# MCU_IO.net
KiCad netlist of a schematic drawn in Altium Designer
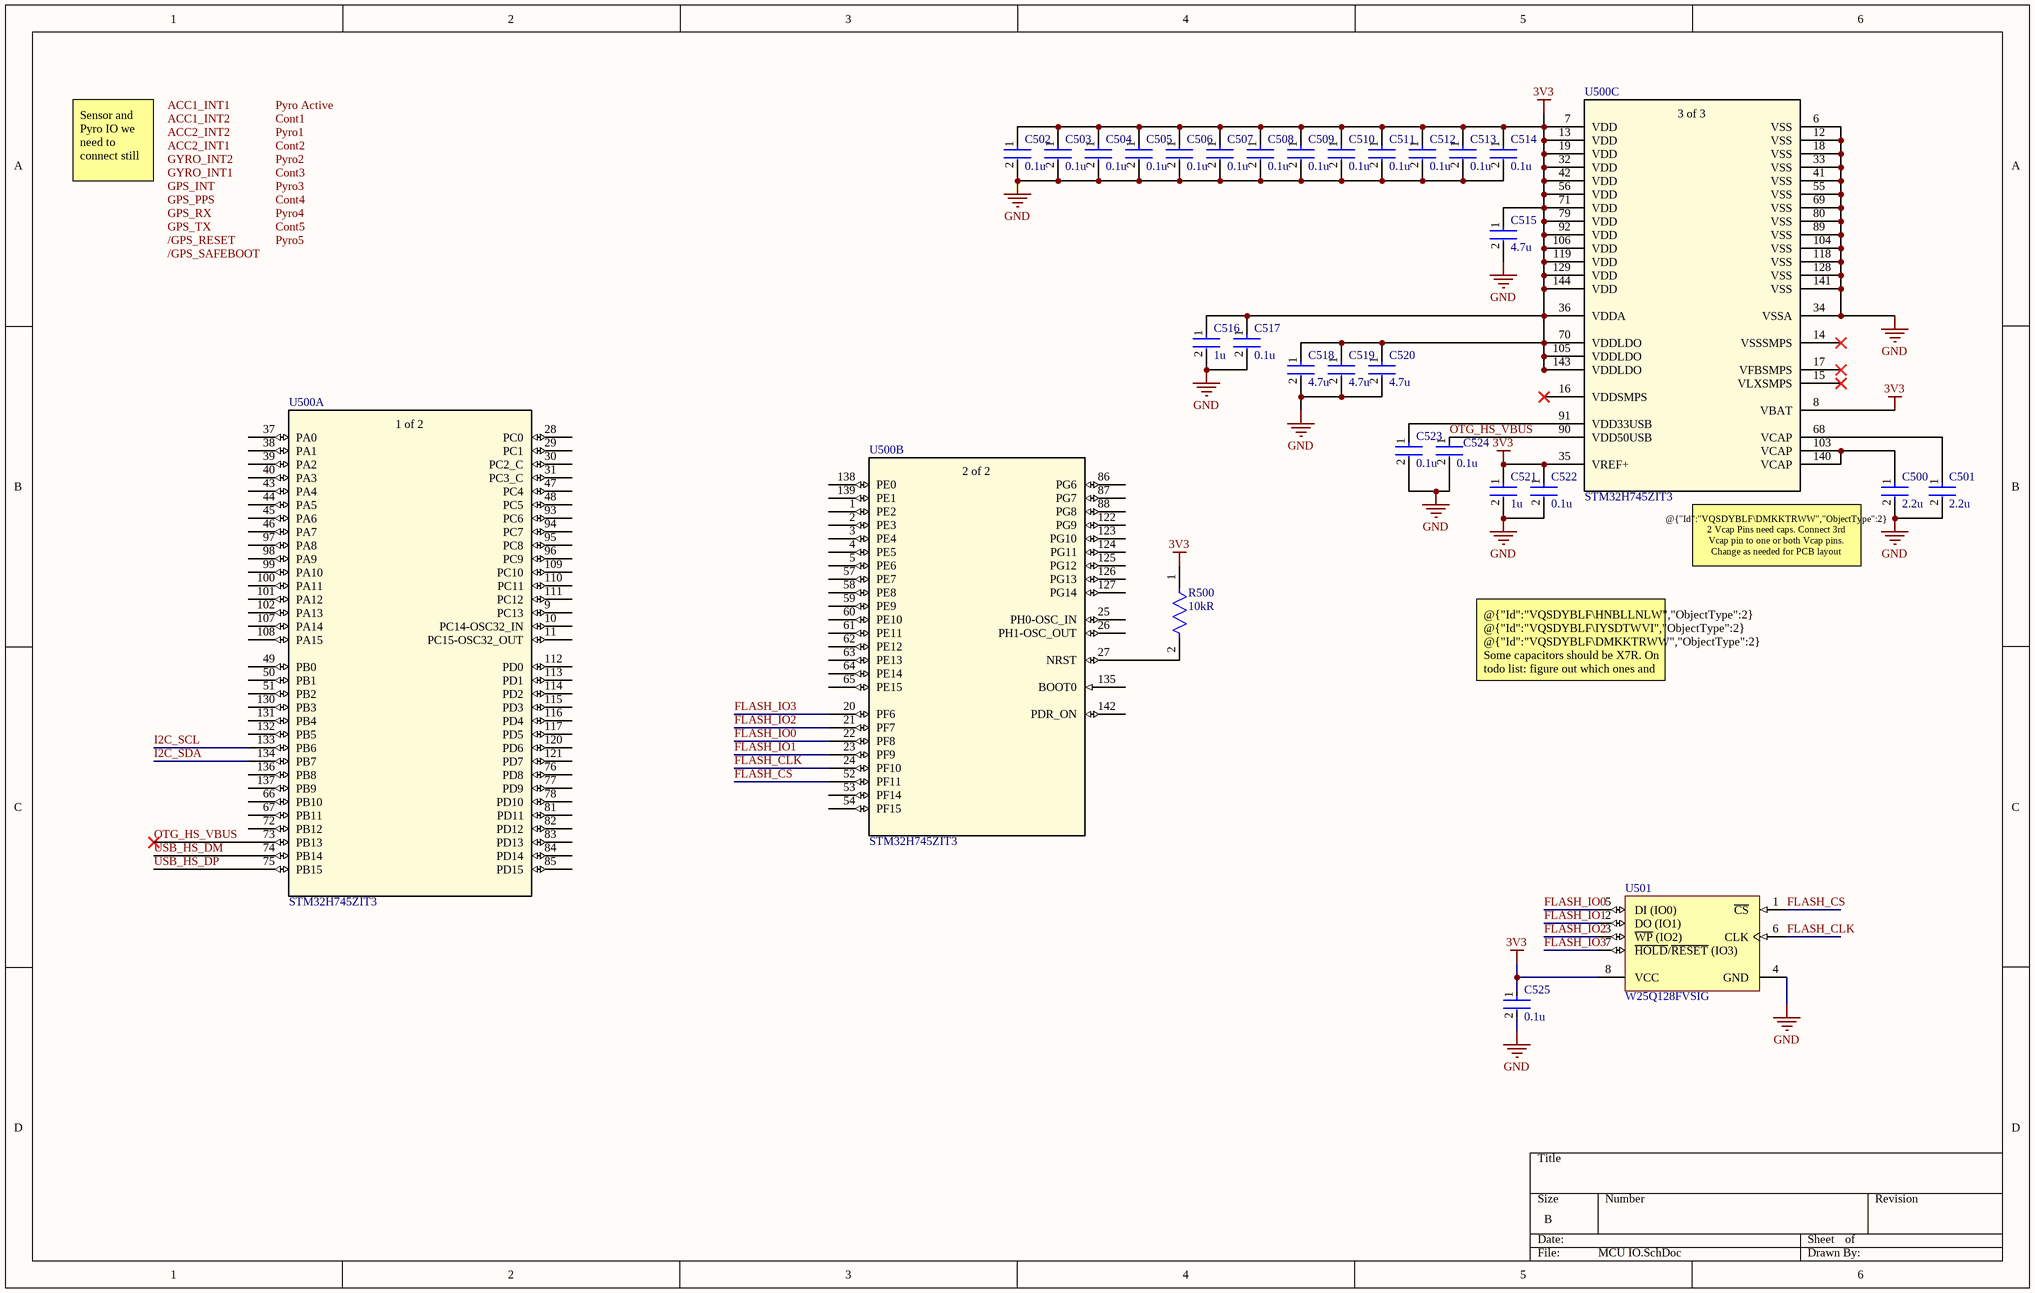
[diagram p0: MCU IO.SchDoc]

(export (version "E")
  (design (tool "Eeschema 10.0.6"))
  (components
    (comp (ref "C500")
      (value "CL10C681JB8NFNC")
      (footprint "FP-CL10-IPC_A")
      (description "Cap Ceramic 680pF 50V C0G ±5% Pad SMD 0603 +125°C T/R")
      (fields (field (name "CAPACITANCE") "2.2u") (field (name "TOLERANCE") "5%"))
      (libsource (lib "Altium Content Vault") (part "b4654b650e69147ec39a6b967a45e02"))
    )
    (comp (ref "C501")
      (value "CL10C681JB8NFNC")
      (footprint "FP-CL10-IPC_A")
      (description "Cap Ceramic 680pF 50V C0G ±5% Pad SMD 0603 +125°C T/R")
      (fields (field (name "CAPACITANCE") "2.2u") (field (name "TOLERANCE") "5%"))
      (libsource (lib "Altium Content Vault") (part "b4654b650e69147ec39a6b967a45e02"))
    )
    (comp (ref "C502")
      (value "CL10C681JB8NFNC")
      (footprint "FP-CL10-IPC_A")
      (description "Cap Ceramic 680pF 50V C0G ±5% Pad SMD 0603 +125°C T/R")
      (fields (field (name "CAPACITANCE") "0.1u") (field (name "TOLERANCE") "5%"))
      (libsource (lib "Altium Content Vault") (part "b4654b650e69147ec39a6b967a45e02"))
    )
    (comp (ref "C503")
      (value "CL10C681JB8NFNC")
      (footprint "FP-CL10-IPC_A")
      (description "Cap Ceramic 680pF 50V C0G ±5% Pad SMD 0603 +125°C T/R")
      (fields (field (name "CAPACITANCE") "0.1u") (field (name "TOLERANCE") "5%"))
      (libsource (lib "Altium Content Vault") (part "b4654b650e69147ec39a6b967a45e02"))
    )
    (comp (ref "C504")
      (value "CL10C681JB8NFNC")
      (footprint "FP-CL10-IPC_A")
      (description "Cap Ceramic 680pF 50V C0G ±5% Pad SMD 0603 +125°C T/R")
      (fields (field (name "CAPACITANCE") "0.1u") (field (name "TOLERANCE") "5%"))
      (libsource (lib "Altium Content Vault") (part "b4654b650e69147ec39a6b967a45e02"))
    )
    (comp (ref "C505")
      (value "CL10C681JB8NFNC")
      (footprint "FP-CL10-IPC_A")
      (description "Cap Ceramic 680pF 50V C0G ±5% Pad SMD 0603 +125°C T/R")
      (fields (field (name "CAPACITANCE") "0.1u") (field (name "TOLERANCE") "5%"))
      (libsource (lib "Altium Content Vault") (part "b4654b650e69147ec39a6b967a45e02"))
    )
    (comp (ref "C506")
      (value "CL10C681JB8NFNC")
      (footprint "FP-CL10-IPC_A")
      (description "Cap Ceramic 680pF 50V C0G ±5% Pad SMD 0603 +125°C T/R")
      (fields (field (name "CAPACITANCE") "0.1u") (field (name "TOLERANCE") "5%"))
      (libsource (lib "Altium Content Vault") (part "b4654b650e69147ec39a6b967a45e02"))
    )
    (comp (ref "C507")
      (value "CL10C681JB8NFNC")
      (footprint "FP-CL10-IPC_A")
      (description "Cap Ceramic 680pF 50V C0G ±5% Pad SMD 0603 +125°C T/R")
      (fields (field (name "CAPACITANCE") "0.1u") (field (name "TOLERANCE") "5%"))
      (libsource (lib "Altium Content Vault") (part "b4654b650e69147ec39a6b967a45e02"))
    )
    (comp (ref "C508")
      (value "CL10C681JB8NFNC")
      (footprint "FP-CL10-IPC_A")
      (description "Cap Ceramic 680pF 50V C0G ±5% Pad SMD 0603 +125°C T/R")
      (fields (field (name "CAPACITANCE") "0.1u") (field (name "TOLERANCE") "5%"))
      (libsource (lib "Altium Content Vault") (part "b4654b650e69147ec39a6b967a45e02"))
    )
    (comp (ref "C509")
      (value "CL10C681JB8NFNC")
      (footprint "FP-CL10-IPC_A")
      (description "Cap Ceramic 680pF 50V C0G ±5% Pad SMD 0603 +125°C T/R")
      (fields (field (name "CAPACITANCE") "0.1u") (field (name "TOLERANCE") "5%"))
      (libsource (lib "Altium Content Vault") (part "b4654b650e69147ec39a6b967a45e02"))
    )
    (comp (ref "C510")
      (value "CL10C681JB8NFNC")
      (footprint "FP-CL10-IPC_A")
      (description "Cap Ceramic 680pF 50V C0G ±5% Pad SMD 0603 +125°C T/R")
      (fields (field (name "CAPACITANCE") "0.1u") (field (name "TOLERANCE") "5%"))
      (libsource (lib "Altium Content Vault") (part "b4654b650e69147ec39a6b967a45e02"))
    )
    (comp (ref "C511")
      (value "CL10C681JB8NFNC")
      (footprint "FP-CL10-IPC_A")
      (description "Cap Ceramic 680pF 50V C0G ±5% Pad SMD 0603 +125°C T/R")
      (fields (field (name "CAPACITANCE") "0.1u") (field (name "TOLERANCE") "5%"))
      (libsource (lib "Altium Content Vault") (part "b4654b650e69147ec39a6b967a45e02"))
    )
    (comp (ref "C512")
      (value "CL10C681JB8NFNC")
      (footprint "FP-CL10-IPC_A")
      (description "Cap Ceramic 680pF 50V C0G ±5% Pad SMD 0603 +125°C T/R")
      (fields (field (name "CAPACITANCE") "0.1u") (field (name "TOLERANCE") "5%"))
      (libsource (lib "Altium Content Vault") (part "b4654b650e69147ec39a6b967a45e02"))
    )
    (comp (ref "C513")
      (value "CL10C681JB8NFNC")
      (footprint "FP-CL10-IPC_A")
      (description "Cap Ceramic 680pF 50V C0G ±5% Pad SMD 0603 +125°C T/R")
      (fields (field (name "CAPACITANCE") "0.1u") (field (name "TOLERANCE") "5%"))
      (libsource (lib "Altium Content Vault") (part "b4654b650e69147ec39a6b967a45e02"))
    )
    (comp (ref "C514")
      (value "CL10C681JB8NFNC")
      (footprint "FP-CL10-IPC_A")
      (description "Cap Ceramic 680pF 50V C0G ±5% Pad SMD 0603 +125°C T/R")
      (fields (field (name "CAPACITANCE") "0.1u") (field (name "TOLERANCE") "5%"))
      (libsource (lib "Altium Content Vault") (part "b4654b650e69147ec39a6b967a45e02"))
    )
    (comp (ref "C515")
      (value "CL10C681JB8NFNC")
      (footprint "FP-CL10-IPC_A")
      (description "Cap Ceramic 680pF 50V C0G ±5% Pad SMD 0603 +125°C T/R")
      (fields (field (name "CAPACITANCE") "4.7u") (field (name "TOLERANCE") "5%"))
      (libsource (lib "Altium Content Vault") (part "b4654b650e69147ec39a6b967a45e02"))
    )
    (comp (ref "C516")
      (value "CL10C681JB8NFNC")
      (footprint "FP-CL10-IPC_A")
      (description "Cap Ceramic 680pF 50V C0G ±5% Pad SMD 0603 +125°C T/R")
      (fields (field (name "CAPACITANCE") "1u") (field (name "TOLERANCE") "5%"))
      (libsource (lib "Altium Content Vault") (part "b4654b650e69147ec39a6b967a45e02"))
    )
    (comp (ref "C517")
      (value "CL10C681JB8NFNC")
      (footprint "FP-CL10-IPC_A")
      (description "Cap Ceramic 680pF 50V C0G ±5% Pad SMD 0603 +125°C T/R")
      (fields (field (name "CAPACITANCE") "0.1u") (field (name "TOLERANCE") "5%"))
      (libsource (lib "Altium Content Vault") (part "b4654b650e69147ec39a6b967a45e02"))
    )
    (comp (ref "C518")
      (value "CL10C681JB8NFNC")
      (footprint "FP-CL10-IPC_A")
      (description "Cap Ceramic 680pF 50V C0G ±5% Pad SMD 0603 +125°C T/R")
      (fields (field (name "CAPACITANCE") "4.7u") (field (name "TOLERANCE") "5%"))
      (libsource (lib "Altium Content Vault") (part "b4654b650e69147ec39a6b967a45e02"))
    )
    (comp (ref "C519")
      (value "CL10C681JB8NFNC")
      (footprint "FP-CL10-IPC_A")
      (description "Cap Ceramic 680pF 50V C0G ±5% Pad SMD 0603 +125°C T/R")
      (fields (field (name "CAPACITANCE") "4.7u") (field (name "TOLERANCE") "5%"))
      (libsource (lib "Altium Content Vault") (part "b4654b650e69147ec39a6b967a45e02"))
    )
    (comp (ref "C520")
      (value "CL10C681JB8NFNC")
      (footprint "FP-CL10-IPC_A")
      (description "Cap Ceramic 680pF 50V C0G ±5% Pad SMD 0603 +125°C T/R")
      (fields (field (name "CAPACITANCE") "4.7u") (field (name "TOLERANCE") "5%"))
      (libsource (lib "Altium Content Vault") (part "b4654b650e69147ec39a6b967a45e02"))
    )
    (comp (ref "C521")
      (value "CL10C681JB8NFNC")
      (footprint "FP-CL10-IPC_A")
      (description "Cap Ceramic 680pF 50V C0G ±5% Pad SMD 0603 +125°C T/R")
      (fields (field (name "CAPACITANCE") "1u") (field (name "TOLERANCE") "5%"))
      (libsource (lib "Altium Content Vault") (part "b4654b650e69147ec39a6b967a45e02"))
    )
    (comp (ref "C522")
      (value "CL10C681JB8NFNC")
      (footprint "FP-CL10-IPC_A")
      (description "Cap Ceramic 680pF 50V C0G ±5% Pad SMD 0603 +125°C T/R")
      (fields (field (name "CAPACITANCE") "0.1u") (field (name "TOLERANCE") "5%"))
      (libsource (lib "Altium Content Vault") (part "b4654b650e69147ec39a6b967a45e02"))
    )
    (comp (ref "C523")
      (value "CL10C681JB8NFNC")
      (footprint "FP-CL10-IPC_A")
      (description "Cap Ceramic 680pF 50V C0G ±5% Pad SMD 0603 +125°C T/R")
      (fields (field (name "CAPACITANCE") "0.1u") (field (name "TOLERANCE") "5%"))
      (libsource (lib "Altium Content Vault") (part "b4654b650e69147ec39a6b967a45e02"))
    )
    (comp (ref "C524")
      (value "CL10C681JB8NFNC")
      (footprint "FP-CL10-IPC_A")
      (description "Cap Ceramic 680pF 50V C0G ±5% Pad SMD 0603 +125°C T/R")
      (fields (field (name "CAPACITANCE") "0.1u") (field (name "TOLERANCE") "5%"))
      (libsource (lib "Altium Content Vault") (part "b4654b650e69147ec39a6b967a45e02"))
    )
    (comp (ref "C525")
      (value "CL10C681JB8NFNC")
      (footprint "FP-CL10-IPC_A")
      (description "Cap Ceramic 680pF 50V C0G ±5% Pad SMD 0603 +125°C T/R")
      (fields (field (name "CAPACITANCE") "0.1u") (field (name "TOLERANCE") "5%"))
      (libsource (lib "Altium Content Vault") (part "b4654b650e69147ec39a6b967a45e02"))
    )
    (comp (ref "R500")
      (value "10kR")
      (footprint "FP-CPF0603-MFG")
      (description "RES SMD 2.15KΩ 0.1% 1/16W 0603")
      (fields
        (field (name "MANUFACTURER") "TE Connectivity")
        (field (name "OCTOPART") "https://octopart.com/cpf0603b2k15e1-te+connectivity-22739551")
      )
      (libsource (lib "Altium Content Vault") (part "1029c3af85768c4190bb7ad29bc67b5"))
    )
    (comp (ref "U500")
      (value "STM32H745ZIT3")
      (footprint "LQFP-144")
      (description "32-bit Dual Core, 144 Pin, 97 IO, 1M RAM, 2M Flash")
      (libsource (lib "Erich Robb") (part "STM32H745ZIT3"))
    )
    (comp (ref "U501")
      (value "W25Q128FVSIG")
      (footprint "WINB-SOIC-8_M")
      (fields (field (name "MANUFACTURER") "Winbond"))
      (libsource (lib "Altium Content Vault") (part "WINB-W25Q128FVSIG-SOIC-8"))
    )
  )
  (nets
    (net (code "11") (name "/FLASH_CLK") (class "Default")
      (node (ref "U500") (pin "24") (pinfunction "PF10_24") (pintype "bidirectional"))
      (node (ref "U501") (pin "6") (pinfunction "CLK_6") (pintype "input"))
    )
    (net (code "12") (name "/FLASH_CS") (class "Default")
      (node (ref "U500") (pin "52") (pinfunction "PF11_52") (pintype "bidirectional"))
      (node (ref "U501") (pin "1") (pinfunction "~{CS}_1") (pintype "input"))
    )
    (net (code "13") (name "/FLASH_IO0") (class "Default")
      (node (ref "U500") (pin "22") (pinfunction "PF8_22") (pintype "bidirectional"))
      (node (ref "U501") (pin "5") (pinfunction "DI_(IO0)_5") (pintype "bidirectional"))
    )
    (net (code "14") (name "/FLASH_IO1") (class "Default")
      (node (ref "U500") (pin "23") (pinfunction "PF9_23") (pintype "bidirectional"))
      (node (ref "U501") (pin "2") (pinfunction "DO_(IO1)_2") (pintype "bidirectional"))
    )
    (net (code "15") (name "/FLASH_IO2") (class "Default")
      (node (ref "U500") (pin "21") (pinfunction "PF7_21") (pintype "bidirectional"))
      (node (ref "U501") (pin "3") (pinfunction "~{WP}_(IO2)_3") (pintype "bidirectional"))
    )
    (net (code "16") (name "/FLASH_IO3") (class "Default")
      (node (ref "U500") (pin "20") (pinfunction "PF6_20") (pintype "bidirectional"))
      (node (ref "U501") (pin "7") (pinfunction "~{HOLD}/~{RESET}_(IO3)_7") (pintype "bidirectional"))
    )
    (net (code "23") (name "/I2C_SCL") (class "Default")
      (node (ref "U500") (pin "133") (pinfunction "PB6_133") (pintype "bidirectional"))
    )
    (net (code "24") (name "/I2C_SDA") (class "Default")
      (node (ref "U500") (pin "134") (pinfunction "PB7_134") (pintype "bidirectional"))
    )
    (net (code "25") (name "/OTG_HS_VBUS") (class "Default")
      (node (ref "C524") (pin "1") (pinfunction "1_1") (pintype "passive"))
      (node (ref "U500") (pin "73") (pinfunction "PB13_73") (pintype "bidirectional"))
      (node (ref "U500") (pin "90") (pinfunction "VDD50USB_90") (pintype "power_in"))
    )
    (net (code "32") (name "/USB_HS_DM") (class "Default")
      (node (ref "U500") (pin "74") (pinfunction "PB14_74") (pintype "bidirectional"))
    )
    (net (code "33") (name "/USB_HS_DP") (class "Default")
      (node (ref "U500") (pin "75") (pinfunction "PB15_75") (pintype "bidirectional"))
    )
    (net (code "36") (name "3V3") (class "Default")
      (node (ref "C502") (pin "1") (pinfunction "1_1") (pintype "passive"))
      (node (ref "C503") (pin "1") (pinfunction "1_1") (pintype "passive"))
      (node (ref "C504") (pin "1") (pinfunction "1_1") (pintype "passive"))
      (node (ref "C505") (pin "1") (pinfunction "1_1") (pintype "passive"))
      (node (ref "C506") (pin "1") (pinfunction "1_1") (pintype "passive"))
      (node (ref "C507") (pin "1") (pinfunction "1_1") (pintype "passive"))
      (node (ref "C508") (pin "1") (pinfunction "1_1") (pintype "passive"))
      (node (ref "C509") (pin "1") (pinfunction "1_1") (pintype "passive"))
      (node (ref "C510") (pin "1") (pinfunction "1_1") (pintype "passive"))
      (node (ref "C511") (pin "1") (pinfunction "1_1") (pintype "passive"))
      (node (ref "C512") (pin "1") (pinfunction "1_1") (pintype "passive"))
      (node (ref "C513") (pin "1") (pinfunction "1_1") (pintype "passive"))
      (node (ref "C514") (pin "1") (pinfunction "1_1") (pintype "passive"))
      (node (ref "C515") (pin "1") (pinfunction "1_1") (pintype "passive"))
      (node (ref "C516") (pin "1") (pinfunction "1_1") (pintype "passive"))
      (node (ref "C517") (pin "1") (pinfunction "1_1") (pintype "passive"))
      (node (ref "C518") (pin "1") (pinfunction "1_1") (pintype "passive"))
      (node (ref "C519") (pin "1") (pinfunction "1_1") (pintype "passive"))
      (node (ref "C520") (pin "1") (pinfunction "1_1") (pintype "passive"))
      (node (ref "C521") (pin "1") (pinfunction "1_1") (pintype "passive"))
      (node (ref "C522") (pin "1") (pinfunction "1_1") (pintype "passive"))
      (node (ref "C525") (pin "1") (pinfunction "1_1") (pintype "passive"))
      (node (ref "R500") (pin "1") (pinfunction "1_1") (pintype "passive"))
      (node (ref "U500") (pin "105") (pinfunction "VDDLDO_105") (pintype "power_in"))
      (node (ref "U500") (pin "106") (pinfunction "VDD_106") (pintype "power_in"))
      (node (ref "U500") (pin "119") (pinfunction "VDD_119") (pintype "power_in"))
      (node (ref "U500") (pin "129") (pinfunction "VDD_129") (pintype "power_in"))
      (node (ref "U500") (pin "13") (pinfunction "VDD_13") (pintype "power_in"))
      (node (ref "U500") (pin "143") (pinfunction "VDDLDO_143") (pintype "power_in"))
      (node (ref "U500") (pin "144") (pinfunction "VDD_144") (pintype "power_in"))
      (node (ref "U500") (pin "19") (pinfunction "VDD_19") (pintype "power_in"))
      (node (ref "U500") (pin "32") (pinfunction "VDD_32") (pintype "power_in"))
      (node (ref "U500") (pin "35") (pinfunction "VREF+_35") (pintype "power_in"))
      (node (ref "U500") (pin "36") (pinfunction "VDDA_36") (pintype "power_in"))
      (node (ref "U500") (pin "42") (pinfunction "VDD_42") (pintype "power_in"))
      (node (ref "U500") (pin "56") (pinfunction "VDD_56") (pintype "power_in"))
      (node (ref "U500") (pin "7") (pinfunction "VDD_7") (pintype "power_in"))
      (node (ref "U500") (pin "70") (pinfunction "VDDLDO_70") (pintype "power_in"))
      (node (ref "U500") (pin "71") (pinfunction "VDD_71") (pintype "power_in"))
      (node (ref "U500") (pin "79") (pinfunction "VDD_79") (pintype "power_in"))
      (node (ref "U500") (pin "8") (pinfunction "VBAT_8") (pintype "power_in"))
      (node (ref "U500") (pin "92") (pinfunction "VDD_92") (pintype "power_in"))
      (node (ref "U501") (pin "8") (pinfunction "VCC_8") (pintype "power_in"))
    )
    (net (code "37") (name "GND") (class "Default")
      (node (ref "C500") (pin "2") (pinfunction "2_2") (pintype "passive"))
      (node (ref "C501") (pin "2") (pinfunction "2_2") (pintype "passive"))
      (node (ref "C502") (pin "2") (pinfunction "2_2") (pintype "passive"))
      (node (ref "C503") (pin "2") (pinfunction "2_2") (pintype "passive"))
      (node (ref "C504") (pin "2") (pinfunction "2_2") (pintype "passive"))
      (node (ref "C505") (pin "2") (pinfunction "2_2") (pintype "passive"))
      (node (ref "C506") (pin "2") (pinfunction "2_2") (pintype "passive"))
      (node (ref "C507") (pin "2") (pinfunction "2_2") (pintype "passive"))
      (node (ref "C508") (pin "2") (pinfunction "2_2") (pintype "passive"))
      (node (ref "C509") (pin "2") (pinfunction "2_2") (pintype "passive"))
      (node (ref "C510") (pin "2") (pinfunction "2_2") (pintype "passive"))
      (node (ref "C511") (pin "2") (pinfunction "2_2") (pintype "passive"))
      (node (ref "C512") (pin "2") (pinfunction "2_2") (pintype "passive"))
      (node (ref "C513") (pin "2") (pinfunction "2_2") (pintype "passive"))
      (node (ref "C514") (pin "2") (pinfunction "2_2") (pintype "passive"))
      (node (ref "C515") (pin "2") (pinfunction "2_2") (pintype "passive"))
      (node (ref "C516") (pin "2") (pinfunction "2_2") (pintype "passive"))
      (node (ref "C517") (pin "2") (pinfunction "2_2") (pintype "passive"))
      (node (ref "C518") (pin "2") (pinfunction "2_2") (pintype "passive"))
      (node (ref "C519") (pin "2") (pinfunction "2_2") (pintype "passive"))
      (node (ref "C520") (pin "2") (pinfunction "2_2") (pintype "passive"))
      (node (ref "C521") (pin "2") (pinfunction "2_2") (pintype "passive"))
      (node (ref "C522") (pin "2") (pinfunction "2_2") (pintype "passive"))
      (node (ref "C523") (pin "2") (pinfunction "2_2") (pintype "passive"))
      (node (ref "C524") (pin "2") (pinfunction "2_2") (pintype "passive"))
      (node (ref "C525") (pin "2") (pinfunction "2_2") (pintype "passive"))
      (node (ref "U500") (pin "104") (pinfunction "VSS_104") (pintype "power_in"))
      (node (ref "U500") (pin "118") (pinfunction "VSS_118") (pintype "power_in"))
      (node (ref "U500") (pin "12") (pinfunction "VSS_12") (pintype "power_in"))
      (node (ref "U500") (pin "128") (pinfunction "VSS_128") (pintype "power_in"))
      (node (ref "U500") (pin "141") (pinfunction "VSS_141") (pintype "power_in"))
      (node (ref "U500") (pin "18") (pinfunction "VSS_18") (pintype "power_in"))
      (node (ref "U500") (pin "33") (pinfunction "VSS_33") (pintype "power_in"))
      (node (ref "U500") (pin "34") (pinfunction "VSSA_34") (pintype "power_in"))
      (node (ref "U500") (pin "41") (pinfunction "VSS_41") (pintype "power_in"))
      (node (ref "U500") (pin "55") (pinfunction "VSS_55") (pintype "power_in"))
      (node (ref "U500") (pin "6") (pinfunction "VSS_6") (pintype "power_in"))
      (node (ref "U500") (pin "69") (pinfunction "VSS_69") (pintype "power_in"))
      (node (ref "U500") (pin "80") (pinfunction "VSS_80") (pintype "power_in"))
      (node (ref "U500") (pin "89") (pinfunction "VSS_89") (pintype "power_in"))
      (node (ref "U501") (pin "4") (pinfunction "GND_4") (pintype "power_in"))
    )
    (net (code "38") (name "Net-(C500-Pad1)") (class "Default")
      (node (ref "C500") (pin "1") (pinfunction "1_1") (pintype "passive"))
      (node (ref "U500") (pin "103") (pinfunction "VCAP_103") (pintype "power_in"))
      (node (ref "U500") (pin "140") (pinfunction "VCAP_140") (pintype "power_in"))
    )
    (net (code "39") (name "Net-(C501-Pad1)") (class "Default")
      (node (ref "C501") (pin "1") (pinfunction "1_1") (pintype "passive"))
      (node (ref "U500") (pin "68") (pinfunction "VCAP_68") (pintype "power_in"))
    )
    (net (code "40") (name "Net-(U500B-NRST)") (class "Default")
      (node (ref "R500") (pin "2") (pinfunction "2_2") (pintype "passive"))
      (node (ref "U500") (pin "27") (pinfunction "NRST_27") (pintype "bidirectional"))
    )
    (net (code "41") (name "Net-(U500C-VDD33USB)") (class "Default")
      (node (ref "C523") (pin "1") (pinfunction "1_1") (pintype "passive"))
      (node (ref "U500") (pin "91") (pinfunction "VDD33USB_91") (pintype "power_in"))
    )
    (net (code "42") (name "unconnected-(U500A-PA0-Pad37)") (class "Default")
      (node (ref "U500") (pin "37") (pinfunction "PA0_37") (pintype "bidirectional"))
    )
    (net (code "43") (name "unconnected-(U500A-PA1-Pad38)") (class "Default")
      (node (ref "U500") (pin "38") (pinfunction "PA1_38") (pintype "bidirectional"))
    )
    (net (code "44") (name "unconnected-(U500A-PA2-Pad39)") (class "Default")
      (node (ref "U500") (pin "39") (pinfunction "PA2_39") (pintype "bidirectional"))
    )
    (net (code "45") (name "unconnected-(U500A-PA3-Pad40)") (class "Default")
      (node (ref "U500") (pin "40") (pinfunction "PA3_40") (pintype "bidirectional"))
    )
    (net (code "46") (name "unconnected-(U500A-PA4-Pad43)") (class "Default")
      (node (ref "U500") (pin "43") (pinfunction "PA4_43") (pintype "bidirectional"))
    )
    (net (code "47") (name "unconnected-(U500A-PA5-Pad44)") (class "Default")
      (node (ref "U500") (pin "44") (pinfunction "PA5_44") (pintype "bidirectional"))
    )
    (net (code "48") (name "unconnected-(U500A-PA6-Pad45)") (class "Default")
      (node (ref "U500") (pin "45") (pinfunction "PA6_45") (pintype "bidirectional"))
    )
    (net (code "49") (name "unconnected-(U500A-PA7-Pad46)") (class "Default")
      (node (ref "U500") (pin "46") (pinfunction "PA7_46") (pintype "bidirectional"))
    )
    (net (code "50") (name "unconnected-(U500A-PA8-Pad97)") (class "Default")
      (node (ref "U500") (pin "97") (pinfunction "PA8_97") (pintype "bidirectional"))
    )
    (net (code "51") (name "unconnected-(U500A-PA9-Pad98)") (class "Default")
      (node (ref "U500") (pin "98") (pinfunction "PA9_98") (pintype "bidirectional"))
    )
    (net (code "52") (name "unconnected-(U500A-PA10-Pad99)") (class "Default")
      (node (ref "U500") (pin "99") (pinfunction "PA10_99") (pintype "bidirectional"))
    )
    (net (code "53") (name "unconnected-(U500A-PA11-Pad100)") (class "Default")
      (node (ref "U500") (pin "100") (pinfunction "PA11_100") (pintype "bidirectional"))
    )
    (net (code "54") (name "unconnected-(U500A-PA12-Pad101)") (class "Default")
      (node (ref "U500") (pin "101") (pinfunction "PA12_101") (pintype "bidirectional"))
    )
    (net (code "55") (name "unconnected-(U500A-PA13-Pad102)") (class "Default")
      (node (ref "U500") (pin "102") (pinfunction "PA13_102") (pintype "bidirectional"))
    )
    (net (code "56") (name "unconnected-(U500A-PA14-Pad107)") (class "Default")
      (node (ref "U500") (pin "107") (pinfunction "PA14_107") (pintype "bidirectional"))
    )
    (net (code "57") (name "unconnected-(U500A-PA15-Pad108)") (class "Default")
      (node (ref "U500") (pin "108") (pinfunction "PA15_108") (pintype "bidirectional"))
    )
    (net (code "58") (name "unconnected-(U500A-PB0-Pad49)") (class "Default")
      (node (ref "U500") (pin "49") (pinfunction "PB0_49") (pintype "bidirectional"))
    )
    (net (code "59") (name "unconnected-(U500A-PB1-Pad50)") (class "Default")
      (node (ref "U500") (pin "50") (pinfunction "PB1_50") (pintype "bidirectional"))
    )
    (net (code "60") (name "unconnected-(U500A-PB2-Pad51)") (class "Default")
      (node (ref "U500") (pin "51") (pinfunction "PB2_51") (pintype "bidirectional"))
    )
    (net (code "61") (name "unconnected-(U500A-PB3-Pad130)") (class "Default")
      (node (ref "U500") (pin "130") (pinfunction "PB3_130") (pintype "bidirectional"))
    )
    (net (code "62") (name "unconnected-(U500A-PB4-Pad131)") (class "Default")
      (node (ref "U500") (pin "131") (pinfunction "PB4_131") (pintype "bidirectional"))
    )
    (net (code "63") (name "unconnected-(U500A-PB5-Pad132)") (class "Default")
      (node (ref "U500") (pin "132") (pinfunction "PB5_132") (pintype "bidirectional"))
    )
    (net (code "64") (name "unconnected-(U500A-PB8-Pad136)") (class "Default")
      (node (ref "U500") (pin "136") (pinfunction "PB8_136") (pintype "bidirectional"))
    )
    (net (code "65") (name "unconnected-(U500A-PB9-Pad137)") (class "Default")
      (node (ref "U500") (pin "137") (pinfunction "PB9_137") (pintype "bidirectional"))
    )
    (net (code "66") (name "unconnected-(U500A-PB10-Pad66)") (class "Default")
      (node (ref "U500") (pin "66") (pinfunction "PB10_66") (pintype "bidirectional"))
    )
    (net (code "67") (name "unconnected-(U500A-PB11-Pad67)") (class "Default")
      (node (ref "U500") (pin "67") (pinfunction "PB11_67") (pintype "bidirectional"))
    )
    (net (code "68") (name "unconnected-(U500A-PB12-Pad72)") (class "Default")
      (node (ref "U500") (pin "72") (pinfunction "PB12_72") (pintype "bidirectional"))
    )
    (net (code "69") (name "unconnected-(U500A-PC0-Pad28)") (class "Default")
      (node (ref "U500") (pin "28") (pinfunction "PC0_28") (pintype "bidirectional"))
    )
    (net (code "70") (name "unconnected-(U500A-PC1-Pad29)") (class "Default")
      (node (ref "U500") (pin "29") (pinfunction "PC1_29") (pintype "bidirectional"))
    )
    (net (code "71") (name "unconnected-(U500A-PC2_C-Pad30)") (class "Default")
      (node (ref "U500") (pin "30") (pinfunction "PC2_C_30") (pintype "bidirectional"))
    )
    (net (code "72") (name "unconnected-(U500A-PC3_C-Pad31)") (class "Default")
      (node (ref "U500") (pin "31") (pinfunction "PC3_C_31") (pintype "bidirectional"))
    )
    (net (code "73") (name "unconnected-(U500A-PC4-Pad47)") (class "Default")
      (node (ref "U500") (pin "47") (pinfunction "PC4_47") (pintype "bidirectional"))
    )
    (net (code "74") (name "unconnected-(U500A-PC5-Pad48)") (class "Default")
      (node (ref "U500") (pin "48") (pinfunction "PC5_48") (pintype "bidirectional"))
    )
    (net (code "75") (name "unconnected-(U500A-PC6-Pad93)") (class "Default")
      (node (ref "U500") (pin "93") (pinfunction "PC6_93") (pintype "bidirectional"))
    )
    (net (code "76") (name "unconnected-(U500A-PC7-Pad94)") (class "Default")
      (node (ref "U500") (pin "94") (pinfunction "PC7_94") (pintype "bidirectional"))
    )
    (net (code "77") (name "unconnected-(U500A-PC8-Pad95)") (class "Default")
      (node (ref "U500") (pin "95") (pinfunction "PC8_95") (pintype "bidirectional"))
    )
    (net (code "78") (name "unconnected-(U500A-PC9-Pad96)") (class "Default")
      (node (ref "U500") (pin "96") (pinfunction "PC9_96") (pintype "bidirectional"))
    )
    (net (code "79") (name "unconnected-(U500A-PC10-Pad109)") (class "Default")
      (node (ref "U500") (pin "109") (pinfunction "PC10_109") (pintype "bidirectional"))
    )
    (net (code "80") (name "unconnected-(U500A-PC11-Pad110)") (class "Default")
      (node (ref "U500") (pin "110") (pinfunction "PC11_110") (pintype "bidirectional"))
    )
    (net (code "81") (name "unconnected-(U500A-PC12-Pad111)") (class "Default")
      (node (ref "U500") (pin "111") (pinfunction "PC12_111") (pintype "bidirectional"))
    )
    (net (code "82") (name "unconnected-(U500A-PC13-Pad9)") (class "Default")
      (node (ref "U500") (pin "9") (pinfunction "PC13_9") (pintype "bidirectional"))
    )
    (net (code "83") (name "unconnected-(U500A-PC14-OSC32_IN-Pad10)") (class "Default")
      (node (ref "U500") (pin "10") (pinfunction "PC14-OSC32_IN_10") (pintype "bidirectional"))
    )
    (net (code "84") (name "unconnected-(U500A-PC15-OSC32_OUT-Pad11)") (class "Default")
      (node (ref "U500") (pin "11") (pinfunction "PC15-OSC32_OUT_11") (pintype "bidirectional"))
    )
    (net (code "85") (name "unconnected-(U500A-PD0-Pad112)") (class "Default")
      (node (ref "U500") (pin "112") (pinfunction "PD0_112") (pintype "bidirectional"))
    )
    (net (code "86") (name "unconnected-(U500A-PD1-Pad113)") (class "Default")
      (node (ref "U500") (pin "113") (pinfunction "PD1_113") (pintype "bidirectional"))
    )
    (net (code "87") (name "unconnected-(U500A-PD2-Pad114)") (class "Default")
      (node (ref "U500") (pin "114") (pinfunction "PD2_114") (pintype "bidirectional"))
    )
    (net (code "88") (name "unconnected-(U500A-PD3-Pad115)") (class "Default")
      (node (ref "U500") (pin "115") (pinfunction "PD3_115") (pintype "bidirectional"))
    )
    (net (code "89") (name "unconnected-(U500A-PD4-Pad116)") (class "Default")
      (node (ref "U500") (pin "116") (pinfunction "PD4_116") (pintype "bidirectional"))
    )
    (net (code "90") (name "unconnected-(U500A-PD5-Pad117)") (class "Default")
      (node (ref "U500") (pin "117") (pinfunction "PD5_117") (pintype "bidirectional"))
    )
    (net (code "91") (name "unconnected-(U500A-PD6-Pad120)") (class "Default")
      (node (ref "U500") (pin "120") (pinfunction "PD6_120") (pintype "bidirectional"))
    )
    (net (code "92") (name "unconnected-(U500A-PD7-Pad121)") (class "Default")
      (node (ref "U500") (pin "121") (pinfunction "PD7_121") (pintype "bidirectional"))
    )
    (net (code "93") (name "unconnected-(U500A-PD8-Pad76)") (class "Default")
      (node (ref "U500") (pin "76") (pinfunction "PD8_76") (pintype "bidirectional"))
    )
    (net (code "94") (name "unconnected-(U500A-PD9-Pad77)") (class "Default")
      (node (ref "U500") (pin "77") (pinfunction "PD9_77") (pintype "bidirectional"))
    )
    (net (code "95") (name "unconnected-(U500A-PD10-Pad78)") (class "Default")
      (node (ref "U500") (pin "78") (pinfunction "PD10_78") (pintype "bidirectional"))
    )
    (net (code "96") (name "unconnected-(U500A-PD11-Pad81)") (class "Default")
      (node (ref "U500") (pin "81") (pinfunction "PD11_81") (pintype "bidirectional"))
    )
    (net (code "97") (name "unconnected-(U500A-PD12-Pad82)") (class "Default")
      (node (ref "U500") (pin "82") (pinfunction "PD12_82") (pintype "bidirectional"))
    )
    (net (code "98") (name "unconnected-(U500A-PD13-Pad83)") (class "Default")
      (node (ref "U500") (pin "83") (pinfunction "PD13_83") (pintype "bidirectional"))
    )
    (net (code "99") (name "unconnected-(U500A-PD14-Pad84)") (class "Default")
      (node (ref "U500") (pin "84") (pinfunction "PD14_84") (pintype "bidirectional"))
    )
    (net (code "100") (name "unconnected-(U500A-PD15-Pad85)") (class "Default")
      (node (ref "U500") (pin "85") (pinfunction "PD15_85") (pintype "bidirectional"))
    )
    (net (code "101") (name "unconnected-(U500B-BOOT0-Pad135)") (class "Default")
      (node (ref "U500") (pin "135") (pinfunction "BOOT0_135") (pintype "input"))
    )
    (net (code "102") (name "unconnected-(U500B-PDR_ON-Pad142)") (class "Default")
      (node (ref "U500") (pin "142") (pinfunction "PDR_ON_142") (pintype "bidirectional"))
    )
    (net (code "103") (name "unconnected-(U500B-PE0-Pad138)") (class "Default")
      (node (ref "U500") (pin "138") (pinfunction "PE0_138") (pintype "bidirectional"))
    )
    (net (code "104") (name "unconnected-(U500B-PE1-Pad139)") (class "Default")
      (node (ref "U500") (pin "139") (pinfunction "PE1_139") (pintype "bidirectional"))
    )
    (net (code "105") (name "unconnected-(U500B-PE2-Pad1)") (class "Default")
      (node (ref "U500") (pin "1") (pinfunction "PE2_1") (pintype "bidirectional"))
    )
    (net (code "106") (name "unconnected-(U500B-PE3-Pad2)") (class "Default")
      (node (ref "U500") (pin "2") (pinfunction "PE3_2") (pintype "bidirectional"))
    )
    (net (code "107") (name "unconnected-(U500B-PE4-Pad3)") (class "Default")
      (node (ref "U500") (pin "3") (pinfunction "PE4_3") (pintype "bidirectional"))
    )
    (net (code "108") (name "unconnected-(U500B-PE5-Pad4)") (class "Default")
      (node (ref "U500") (pin "4") (pinfunction "PE5_4") (pintype "bidirectional"))
    )
    (net (code "109") (name "unconnected-(U500B-PE6-Pad5)") (class "Default")
      (node (ref "U500") (pin "5") (pinfunction "PE6_5") (pintype "bidirectional"))
    )
    (net (code "110") (name "unconnected-(U500B-PE7-Pad57)") (class "Default")
      (node (ref "U500") (pin "57") (pinfunction "PE7_57") (pintype "bidirectional"))
    )
    (net (code "111") (name "unconnected-(U500B-PE8-Pad58)") (class "Default")
      (node (ref "U500") (pin "58") (pinfunction "PE8_58") (pintype "bidirectional"))
    )
    (net (code "112") (name "unconnected-(U500B-PE9-Pad59)") (class "Default")
      (node (ref "U500") (pin "59") (pinfunction "PE9_59") (pintype "bidirectional"))
    )
    (net (code "113") (name "unconnected-(U500B-PE10-Pad60)") (class "Default")
      (node (ref "U500") (pin "60") (pinfunction "PE10_60") (pintype "bidirectional"))
    )
    (net (code "114") (name "unconnected-(U500B-PE11-Pad61)") (class "Default")
      (node (ref "U500") (pin "61") (pinfunction "PE11_61") (pintype "bidirectional"))
    )
    (net (code "115") (name "unconnected-(U500B-PE12-Pad62)") (class "Default")
      (node (ref "U500") (pin "62") (pinfunction "PE12_62") (pintype "bidirectional"))
    )
    (net (code "116") (name "unconnected-(U500B-PE13-Pad63)") (class "Default")
      (node (ref "U500") (pin "63") (pinfunction "PE13_63") (pintype "bidirectional"))
    )
    (net (code "117") (name "unconnected-(U500B-PE14-Pad64)") (class "Default")
      (node (ref "U500") (pin "64") (pinfunction "PE14_64") (pintype "bidirectional"))
    )
    (net (code "118") (name "unconnected-(U500B-PE15-Pad65)") (class "Default")
      (node (ref "U500") (pin "65") (pinfunction "PE15_65") (pintype "bidirectional"))
    )
    (net (code "119") (name "unconnected-(U500B-PF14-Pad53)") (class "Default")
      (node (ref "U500") (pin "53") (pinfunction "PF14_53") (pintype "bidirectional"))
    )
    (net (code "120") (name "unconnected-(U500B-PF15-Pad54)") (class "Default")
      (node (ref "U500") (pin "54") (pinfunction "PF15_54") (pintype "bidirectional"))
    )
    (net (code "121") (name "unconnected-(U500B-PG6-Pad86)") (class "Default")
      (node (ref "U500") (pin "86") (pinfunction "PG6_86") (pintype "bidirectional"))
    )
    (net (code "122") (name "unconnected-(U500B-PG7-Pad87)") (class "Default")
      (node (ref "U500") (pin "87") (pinfunction "PG7_87") (pintype "bidirectional"))
    )
    (net (code "123") (name "unconnected-(U500B-PG8-Pad88)") (class "Default")
      (node (ref "U500") (pin "88") (pinfunction "PG8_88") (pintype "bidirectional"))
    )
    (net (code "124") (name "unconnected-(U500B-PG9-Pad122)") (class "Default")
      (node (ref "U500") (pin "122") (pinfunction "PG9_122") (pintype "bidirectional"))
    )
    (net (code "125") (name "unconnected-(U500B-PG10-Pad123)") (class "Default")
      (node (ref "U500") (pin "123") (pinfunction "PG10_123") (pintype "bidirectional"))
    )
    (net (code "126") (name "unconnected-(U500B-PG11-Pad124)") (class "Default")
      (node (ref "U500") (pin "124") (pinfunction "PG11_124") (pintype "bidirectional"))
    )
    (net (code "127") (name "unconnected-(U500B-PG12-Pad125)") (class "Default")
      (node (ref "U500") (pin "125") (pinfunction "PG12_125") (pintype "bidirectional"))
    )
    (net (code "128") (name "unconnected-(U500B-PG13-Pad126)") (class "Default")
      (node (ref "U500") (pin "126") (pinfunction "PG13_126") (pintype "bidirectional"))
    )
    (net (code "129") (name "unconnected-(U500B-PG14-Pad127)") (class "Default")
      (node (ref "U500") (pin "127") (pinfunction "PG14_127") (pintype "bidirectional"))
    )
    (net (code "130") (name "unconnected-(U500B-PH0-OSC_IN-Pad25)") (class "Default")
      (node (ref "U500") (pin "25") (pinfunction "PH0-OSC_IN_25") (pintype "bidirectional"))
    )
    (net (code "131") (name "unconnected-(U500B-PH1-OSC_OUT-Pad26)") (class "Default")
      (node (ref "U500") (pin "26") (pinfunction "PH1-OSC_OUT_26") (pintype "bidirectional"))
    )
    (net (code "132") (name "unconnected-(U500C-VDDSMPS-Pad16)") (class "Default")
      (node (ref "U500") (pin "16") (pinfunction "VDDSMPS_16") (pintype "power_in+no_connect"))
    )
    (net (code "133") (name "unconnected-(U500C-VFBSMPS-Pad17)") (class "Default")
      (node (ref "U500") (pin "17") (pinfunction "VFBSMPS_17") (pintype "power_in+no_connect"))
    )
    (net (code "134") (name "unconnected-(U500C-VLXSMPS-Pad15)") (class "Default")
      (node (ref "U500") (pin "15") (pinfunction "VLXSMPS_15") (pintype "power_in+no_connect"))
    )
    (net (code "135") (name "unconnected-(U500C-VSSSMPS-Pad14)") (class "Default")
      (node (ref "U500") (pin "14") (pinfunction "VSSSMPS_14") (pintype "power_in+no_connect"))
    )
  )
)
